# 11_DAC.net
KiCad netlist of a schematic drawn in Altium Designer
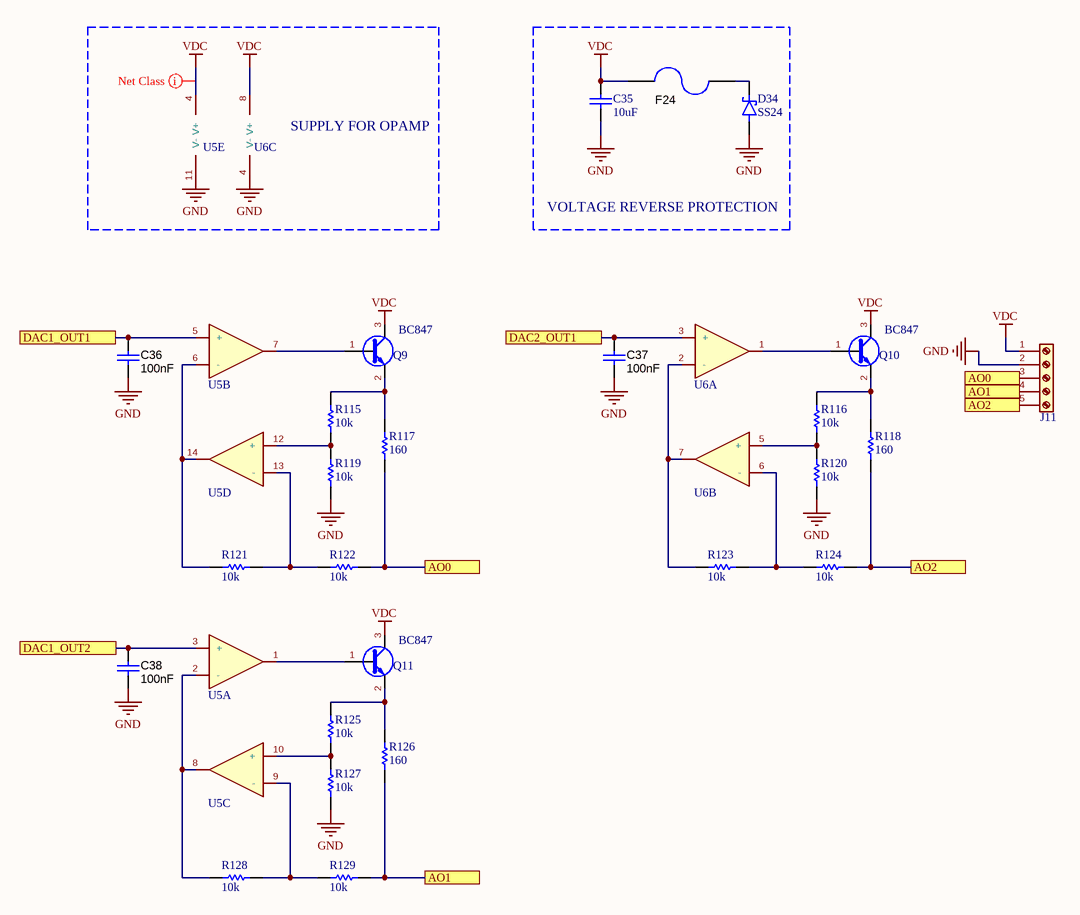
[diagram p0: 11_DAC.SchDoc]

(export (version "E")
  (design (tool "Eeschema 10.0.6"))
  (components
    (comp (ref "C35")
      (value "CGA6P1X7R1E106M250AC")
      (footprint "C_1206_3216Metric")
      (fields
        (field (name "MANUFACTURER") "TDK")
        (field (name "VALUEDISPLAYED") "10uF")
        (field (name "PUBLISHER") "Texas Instruments")
      )
      (libsource (lib "PROC051C_AWR1843BOOST_RevC") (part "CAP 10uF 1206"))
    )
    (comp (ref "C36")
      (value "CAP 100nF 0603")
      (footprint "0603")
      (description "CAP, CERM, 100 nF, 25 V, +/- 10%, X7R, AEC-Q200 Grade 1, 0603")
      (fields
        (field (name "MANUFACTURER") "MuRata")
        (field (name "PARTNUMBER") "GCM188R70J225KE22D")
        (field (name "VALUEDISPLAYED") "100nF")
        (field (name "PUBLISHER") "Texas Instruments")
      )
      (libsource (lib "PROC051C_AWR1843BOOST_RevC") (part "CAP 100nF 0603"))
    )
    (comp (ref "C37")
      (value "CAP 100nF 0603")
      (footprint "0603")
      (description "CAP, CERM, 100 nF, 25 V, +/- 10%, X7R, AEC-Q200 Grade 1, 0603")
      (fields
        (field (name "MANUFACTURER") "MuRata")
        (field (name "PARTNUMBER") "GCM188R70J225KE22D")
        (field (name "VALUEDISPLAYED") "100nF")
        (field (name "PUBLISHER") "Texas Instruments")
      )
      (libsource (lib "PROC051C_AWR1843BOOST_RevC") (part "CAP 100nF 0603"))
    )
    (comp (ref "C38")
      (value "CAP 100nF 0603")
      (footprint "0603")
      (description "CAP, CERM, 100 nF, 25 V, +/- 10%, X7R, AEC-Q200 Grade 1, 0603")
      (fields
        (field (name "MANUFACTURER") "MuRata")
        (field (name "PARTNUMBER") "GCM188R70J225KE22D")
        (field (name "VALUEDISPLAYED") "100nF")
        (field (name "PUBLISHER") "Texas Instruments")
      )
      (libsource (lib "PROC051C_AWR1843BOOST_RevC") (part "CAP 100nF 0603"))
    )
    (comp (ref "D34")
      (value "SS24")
      (footprint "DIOM5336X265N")
      (description "Diode Schottky 40V 2A Surface Mount DO-214AA (SMB)")
      (fields (field (name "MF") "ON Semiconductor"))
      (libsource (lib "PROC051C_AWR1843BOOST_RevC") (part "SS24"))
    )
    (comp (ref "F24")
      (value "0440005.WR")
      (footprint "CAPC4520X203N")
      (description "Fuse, 5 A, 32VAC/VDC, SMD")
      (fields (field (name "MANUFACTURER") "Littelfuse"))
      (libsource (lib "PROC051C_AWR1843BOOST_RevC") (part "FUSE 1808"))
    )
    (comp (ref "J11")
      (value "Terminal_01x5_P5.00")
      (footprint "TerminalBlock_Phoenix_PT-1,5-5-5.0-H_1x5_P5.00mm_Horizontal")
      (libsource (lib "PROC051C_AWR1843BOOST_RevC") (part "Terminal_01x5_P5.00"))
    )
    (comp (ref "Q9")
      (value "BC847")
      (footprint "SOT-23")
      (libsource (lib "PROC051C_AWR1843BOOST_RevC") (part "BC847"))
    )
    (comp (ref "Q10")
      (value "BC847")
      (footprint "SOT-23")
      (libsource (lib "PROC051C_AWR1843BOOST_RevC") (part "BC847"))
    )
    (comp (ref "Q11")
      (value "BC847")
      (footprint "SOT-23")
      (libsource (lib "PROC051C_AWR1843BOOST_RevC") (part "BC847"))
    )
    (comp (ref "R115")
      (value "RES 10K 0603")
      (footprint "0603")
      (description "RES, 10K, 1%, 0.1 W, AEC-Q200 Grade 0, 0603")
      (fields
        (field (name "MANUFACTURER") "Vishay-Dale")
        (field (name "PARTNUMBER") "CRCW060320R0JNEA")
        (field (name "VALUEDISPLAYED") "10k")
      )
      (libsource (lib "PROC051C_AWR1843BOOST_RevC") (part "RES 10K 0603 1%"))
    )
    (comp (ref "R116")
      (value "RES 10K 0603")
      (footprint "0603")
      (description "RES, 10K, 1%, 0.1 W, AEC-Q200 Grade 0, 0603")
      (fields
        (field (name "MANUFACTURER") "Vishay-Dale")
        (field (name "PARTNUMBER") "CRCW060320R0JNEA")
        (field (name "VALUEDISPLAYED") "10k")
      )
      (libsource (lib "PROC051C_AWR1843BOOST_RevC") (part "RES 10K 0603 1%"))
    )
    (comp (ref "R117")
      (value "CRCW060320R0JNEA")
      (footprint "0603")
      (description "RES, 160, 5%, 0.1 W, AEC-Q200 Grade 0, 0603")
      (fields (field (name "MANUFACTURER") "Vishay-Dale") (field (name "VALUEDISPLAYED") "160"))
      (libsource (lib "PROC051C_AWR1843BOOST_RevC") (part "RES 160R 0603"))
    )
    (comp (ref "R118")
      (value "CRCW060320R0JNEA")
      (footprint "0603")
      (description "RES, 160, 5%, 0.1 W, AEC-Q200 Grade 0, 0603")
      (fields (field (name "MANUFACTURER") "Vishay-Dale") (field (name "VALUEDISPLAYED") "160"))
      (libsource (lib "PROC051C_AWR1843BOOST_RevC") (part "RES 160R 0603"))
    )
    (comp (ref "R119")
      (value "RES 10K 0603")
      (footprint "0603")
      (description "RES, 10K, 1%, 0.1 W, AEC-Q200 Grade 0, 0603")
      (fields
        (field (name "MANUFACTURER") "Vishay-Dale")
        (field (name "PARTNUMBER") "CRCW060320R0JNEA")
        (field (name "VALUEDISPLAYED") "10k")
      )
      (libsource (lib "PROC051C_AWR1843BOOST_RevC") (part "RES 10K 0603 1%"))
    )
    (comp (ref "R120")
      (value "RES 10K 0603")
      (footprint "0603")
      (description "RES, 10K, 1%, 0.1 W, AEC-Q200 Grade 0, 0603")
      (fields
        (field (name "MANUFACTURER") "Vishay-Dale")
        (field (name "PARTNUMBER") "CRCW060320R0JNEA")
        (field (name "VALUEDISPLAYED") "10k")
      )
      (libsource (lib "PROC051C_AWR1843BOOST_RevC") (part "RES 10K 0603 1%"))
    )
    (comp (ref "R121")
      (value "RES 10K 0603")
      (footprint "0603")
      (description "RES, 10K, 1%, 0.1 W, AEC-Q200 Grade 0, 0603")
      (fields
        (field (name "MANUFACTURER") "Vishay-Dale")
        (field (name "PARTNUMBER") "CRCW060320R0JNEA")
        (field (name "VALUEDISPLAYED") "10k")
      )
      (libsource (lib "PROC051C_AWR1843BOOST_RevC") (part "RES 10K 0603 1%"))
    )
    (comp (ref "R122")
      (value "RES 10K 0603")
      (footprint "0603")
      (description "RES, 10K, 1%, 0.1 W, AEC-Q200 Grade 0, 0603")
      (fields
        (field (name "MANUFACTURER") "Vishay-Dale")
        (field (name "PARTNUMBER") "CRCW060320R0JNEA")
        (field (name "VALUEDISPLAYED") "10k")
      )
      (libsource (lib "PROC051C_AWR1843BOOST_RevC") (part "RES 10K 0603 1%"))
    )
    (comp (ref "R123")
      (value "RES 10K 0603")
      (footprint "0603")
      (description "RES, 10K, 1%, 0.1 W, AEC-Q200 Grade 0, 0603")
      (fields
        (field (name "MANUFACTURER") "Vishay-Dale")
        (field (name "PARTNUMBER") "CRCW060320R0JNEA")
        (field (name "VALUEDISPLAYED") "10k")
      )
      (libsource (lib "PROC051C_AWR1843BOOST_RevC") (part "RES 10K 0603 1%"))
    )
    (comp (ref "R124")
      (value "RES 10K 0603")
      (footprint "0603")
      (description "RES, 10K, 1%, 0.1 W, AEC-Q200 Grade 0, 0603")
      (fields
        (field (name "MANUFACTURER") "Vishay-Dale")
        (field (name "PARTNUMBER") "CRCW060320R0JNEA")
        (field (name "VALUEDISPLAYED") "10k")
      )
      (libsource (lib "PROC051C_AWR1843BOOST_RevC") (part "RES 10K 0603 1%"))
    )
    (comp (ref "R125")
      (value "RES 10K 0603")
      (footprint "0603")
      (description "RES, 10K, 1%, 0.1 W, AEC-Q200 Grade 0, 0603")
      (fields
        (field (name "MANUFACTURER") "Vishay-Dale")
        (field (name "PARTNUMBER") "CRCW060320R0JNEA")
        (field (name "VALUEDISPLAYED") "10k")
      )
      (libsource (lib "PROC051C_AWR1843BOOST_RevC") (part "RES 10K 0603 1%"))
    )
    (comp (ref "R126")
      (value "CRCW060320R0JNEA")
      (footprint "0603")
      (description "RES, 160, 5%, 0.1 W, AEC-Q200 Grade 0, 0603")
      (fields (field (name "MANUFACTURER") "Vishay-Dale") (field (name "VALUEDISPLAYED") "160"))
      (libsource (lib "PROC051C_AWR1843BOOST_RevC") (part "RES 160R 0603"))
    )
    (comp (ref "R127")
      (value "RES 10K 0603")
      (footprint "0603")
      (description "RES, 10K, 1%, 0.1 W, AEC-Q200 Grade 0, 0603")
      (fields
        (field (name "MANUFACTURER") "Vishay-Dale")
        (field (name "PARTNUMBER") "CRCW060320R0JNEA")
        (field (name "VALUEDISPLAYED") "10k")
      )
      (libsource (lib "PROC051C_AWR1843BOOST_RevC") (part "RES 10K 0603 1%"))
    )
    (comp (ref "R128")
      (value "RES 10K 0603")
      (footprint "0603")
      (description "RES, 10K, 1%, 0.1 W, AEC-Q200 Grade 0, 0603")
      (fields
        (field (name "MANUFACTURER") "Vishay-Dale")
        (field (name "PARTNUMBER") "CRCW060320R0JNEA")
        (field (name "VALUEDISPLAYED") "10k")
      )
      (libsource (lib "PROC051C_AWR1843BOOST_RevC") (part "RES 10K 0603 1%"))
    )
    (comp (ref "R129")
      (value "RES 10K 0603")
      (footprint "0603")
      (description "RES, 10K, 1%, 0.1 W, AEC-Q200 Grade 0, 0603")
      (fields
        (field (name "MANUFACTURER") "Vishay-Dale")
        (field (name "PARTNUMBER") "CRCW060320R0JNEA")
        (field (name "VALUEDISPLAYED") "10k")
      )
      (libsource (lib "PROC051C_AWR1843BOOST_RevC") (part "RES 10K 0603 1%"))
    )
    (comp (ref "U5")
      (value "LM2902")
      (footprint "SOIC-14_3.9x8.7mm_P1.27mm")
      (libsource (lib "PROC051C_AWR1843BOOST_RevC") (part "LM2902"))
    )
    (comp (ref "U6")
      (value "LM2904")
      (footprint "SOIC-8_3.9x4.9mm_P1.27mm")
      (libsource (lib "PROC051C_AWR1843BOOST_RevC") (part "LM2904"))
    )
  )
  (nets
    (net (code "1") (name "/AO0") (class "Default")
      (node (ref "J11") (pin "3") (pinfunction "Pin_3_3") (pintype "passive"))
      (node (ref "R117") (pin "1") (pinfunction "1_1") (pintype "passive"))
      (node (ref "R122") (pin "2") (pinfunction "2_2") (pintype "passive"))
    )
    (net (code "2") (name "/AO1") (class "Default")
      (node (ref "J11") (pin "4") (pinfunction "Pin_4_4") (pintype "passive"))
      (node (ref "R126") (pin "1") (pinfunction "1_1") (pintype "passive"))
      (node (ref "R129") (pin "2") (pinfunction "2_2") (pintype "passive"))
    )
    (net (code "3") (name "/AO2") (class "Default")
      (node (ref "J11") (pin "5") (pinfunction "Pin_5_5") (pintype "passive"))
      (node (ref "R118") (pin "1") (pinfunction "1_1") (pintype "passive"))
      (node (ref "R124") (pin "2") (pinfunction "2_2") (pintype "passive"))
    )
    (net (code "4") (name "/DAC1_OUT1") (class "Default")
      (node (ref "C36") (pin "1") (pinfunction "1_1") (pintype "passive"))
      (node (ref "U5") (pin "5") (pinfunction "+_5") (pintype "passive"))
    )
    (net (code "5") (name "/DAC1_OUT2") (class "Default")
      (node (ref "C38") (pin "1") (pinfunction "1_1") (pintype "passive"))
      (node (ref "U5") (pin "3") (pinfunction "+_3") (pintype "passive"))
    )
    (net (code "6") (name "/DAC2_OUT1") (class "Default")
      (node (ref "C37") (pin "1") (pinfunction "1_1") (pintype "passive"))
      (node (ref "U6") (pin "3") (pinfunction "+_3") (pintype "passive"))
    )
    (net (code "7") (name "GND") (class "Default")
      (node (ref "C35") (pin "2") (pinfunction "2_2") (pintype "passive"))
      (node (ref "C36") (pin "2") (pinfunction "2_2") (pintype "passive"))
      (node (ref "C37") (pin "2") (pinfunction "2_2") (pintype "passive"))
      (node (ref "C38") (pin "2") (pinfunction "2_2") (pintype "passive"))
      (node (ref "D34") (pin "A") (pinfunction "A_A") (pintype "passive"))
      (node (ref "J11") (pin "2") (pinfunction "Pin_2_2") (pintype "passive"))
      (node (ref "R119") (pin "1") (pinfunction "1_1") (pintype "passive"))
      (node (ref "R120") (pin "1") (pinfunction "1_1") (pintype "passive"))
      (node (ref "R127") (pin "1") (pinfunction "1_1") (pintype "passive"))
      (node (ref "U5") (pin "11") (pinfunction "V-_11") (pintype "passive"))
      (node (ref "U6") (pin "4") (pinfunction "V-_4") (pintype "passive"))
    )
    (net (code "8") (name "Net-(D34-K)") (class "Default")
      (node (ref "D34") (pin "C") (pinfunction "K_C") (pintype "passive"))
      (node (ref "F24") (pin "1") (pinfunction "1_1") (pintype "passive"))
    )
    (net (code "9") (name "Net-(Q9-B)") (class "Default")
      (node (ref "Q9") (pin "1") (pinfunction "B_1") (pintype "passive"))
      (node (ref "U5") (pin "7") (pinfunction "7_7") (pintype "passive"))
    )
    (net (code "10") (name "Net-(Q9-E)") (class "Default")
      (node (ref "Q9") (pin "2") (pinfunction "E_2") (pintype "passive"))
      (node (ref "R115") (pin "2") (pinfunction "2_2") (pintype "passive"))
      (node (ref "R117") (pin "2") (pinfunction "2_2") (pintype "passive"))
    )
    (net (code "11") (name "Net-(Q10-B)") (class "Default")
      (node (ref "Q10") (pin "1") (pinfunction "B_1") (pintype "passive"))
      (node (ref "U6") (pin "1") (pinfunction "1_1") (pintype "passive"))
    )
    (net (code "12") (name "Net-(Q10-E)") (class "Default")
      (node (ref "Q10") (pin "2") (pinfunction "E_2") (pintype "passive"))
      (node (ref "R116") (pin "2") (pinfunction "2_2") (pintype "passive"))
      (node (ref "R118") (pin "2") (pinfunction "2_2") (pintype "passive"))
    )
    (net (code "13") (name "Net-(Q11-B)") (class "Default")
      (node (ref "Q11") (pin "1") (pinfunction "B_1") (pintype "passive"))
      (node (ref "U5") (pin "1") (pinfunction "1_1") (pintype "passive"))
    )
    (net (code "14") (name "Net-(Q11-E)") (class "Default")
      (node (ref "Q11") (pin "2") (pinfunction "E_2") (pintype "passive"))
      (node (ref "R125") (pin "2") (pinfunction "2_2") (pintype "passive"))
      (node (ref "R126") (pin "2") (pinfunction "2_2") (pintype "passive"))
    )
    (net (code "15") (name "Net-(U5A--)") (class "Default")
      (node (ref "R128") (pin "1") (pinfunction "1_1") (pintype "passive"))
      (node (ref "U5") (pin "2") (pinfunction "-_2") (pintype "passive"))
      (node (ref "U5") (pin "8") (pinfunction "8_8") (pintype "passive"))
    )
    (net (code "16") (name "Net-(U5B--)") (class "Default")
      (node (ref "R121") (pin "1") (pinfunction "1_1") (pintype "passive"))
      (node (ref "U5") (pin "14") (pinfunction "14_14") (pintype "passive"))
      (node (ref "U5") (pin "6") (pinfunction "-_6") (pintype "passive"))
    )
    (net (code "17") (name "Net-(U5C-+)") (class "Default")
      (node (ref "R125") (pin "1") (pinfunction "1_1") (pintype "passive"))
      (node (ref "R127") (pin "2") (pinfunction "2_2") (pintype "passive"))
      (node (ref "U5") (pin "10") (pinfunction "+_10") (pintype "passive"))
    )
    (net (code "18") (name "Net-(U5C--)") (class "Default")
      (node (ref "R128") (pin "2") (pinfunction "2_2") (pintype "passive"))
      (node (ref "R129") (pin "1") (pinfunction "1_1") (pintype "passive"))
      (node (ref "U5") (pin "9") (pinfunction "-_9") (pintype "passive"))
    )
    (net (code "19") (name "Net-(U5D-+)") (class "Default")
      (node (ref "R115") (pin "1") (pinfunction "1_1") (pintype "passive"))
      (node (ref "R119") (pin "2") (pinfunction "2_2") (pintype "passive"))
      (node (ref "U5") (pin "12") (pinfunction "+_12") (pintype "passive"))
    )
    (net (code "20") (name "Net-(U5D--)") (class "Default")
      (node (ref "R121") (pin "2") (pinfunction "2_2") (pintype "passive"))
      (node (ref "R122") (pin "1") (pinfunction "1_1") (pintype "passive"))
      (node (ref "U5") (pin "13") (pinfunction "-_13") (pintype "passive"))
    )
    (net (code "21") (name "Net-(U6A--)") (class "Default")
      (node (ref "R123") (pin "1") (pinfunction "1_1") (pintype "passive"))
      (node (ref "U6") (pin "2") (pinfunction "-_2") (pintype "passive"))
      (node (ref "U6") (pin "7") (pinfunction "7_7") (pintype "passive"))
    )
    (net (code "22") (name "Net-(U6B-+)") (class "Default")
      (node (ref "R116") (pin "1") (pinfunction "1_1") (pintype "passive"))
      (node (ref "R120") (pin "2") (pinfunction "2_2") (pintype "passive"))
      (node (ref "U6") (pin "5") (pinfunction "+_5") (pintype "passive"))
    )
    (net (code "23") (name "Net-(U6B--)") (class "Default")
      (node (ref "R123") (pin "2") (pinfunction "2_2") (pintype "passive"))
      (node (ref "R124") (pin "1") (pinfunction "1_1") (pintype "passive"))
      (node (ref "U6") (pin "6") (pinfunction "-_6") (pintype "passive"))
    )
    (net (code "24") (name "VDC") (class "Default")
      (node (ref "C35") (pin "1") (pinfunction "1_1") (pintype "passive"))
      (node (ref "F24") (pin "2") (pinfunction "2_2") (pintype "passive"))
      (node (ref "J11") (pin "1") (pinfunction "Pin_1_1") (pintype "passive"))
      (node (ref "Q10") (pin "3") (pinfunction "C_3") (pintype "passive"))
      (node (ref "Q11") (pin "3") (pinfunction "C_3") (pintype "passive"))
      (node (ref "Q9") (pin "3") (pinfunction "C_3") (pintype "passive"))
      (node (ref "U5") (pin "4") (pinfunction "V+_4") (pintype "passive"))
      (node (ref "U6") (pin "8") (pinfunction "V+_8") (pintype "passive"))
    )
  )
)
